# Kalibracija2.net
KiCad netlist of a schematic drawn in Altium Designer
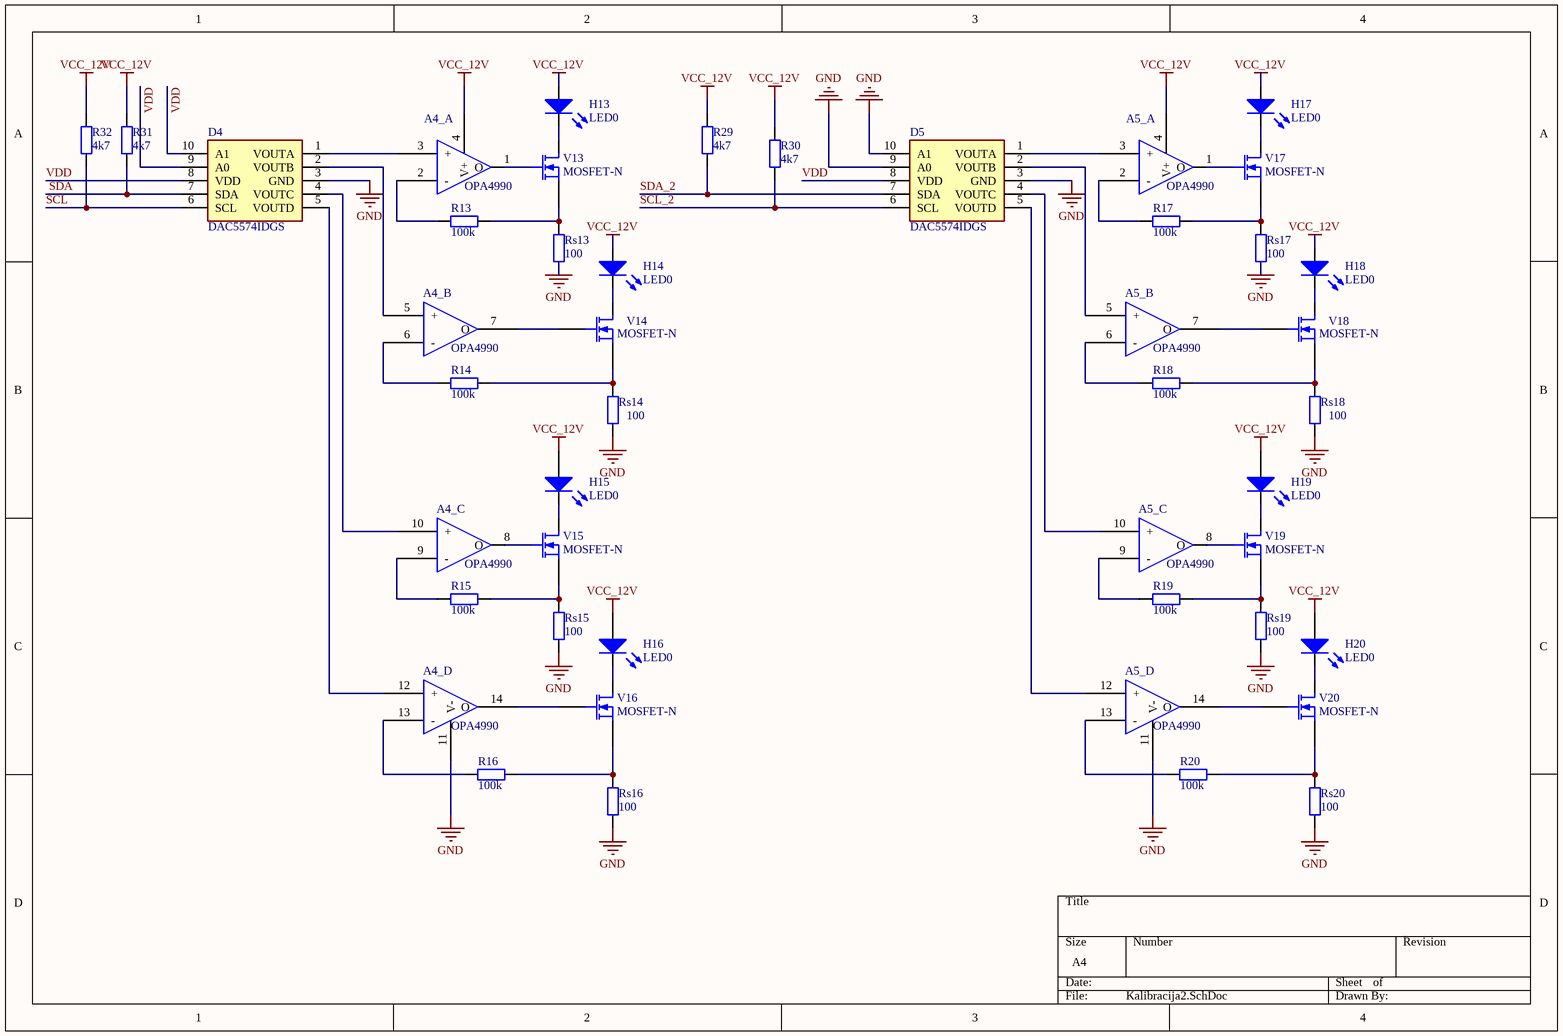
[diagram p0: Kalibracija2.SchDoc]

(export (version "E")
  (design (tool "Eeschema 10.0.6"))
  (components
    (comp (ref "A4_")
      (value "OPA4990")
      (footprint "SOIC127P600X175-14N")
      (libsource (lib "Kalibracija") (part "OPA4990"))
    )
    (comp (ref "A5_")
      (value "OPA4990")
      (footprint "SOIC127P600X175-14N")
      (libsource (lib "Kalibracija") (part "OPA4990"))
    )
    (comp (ref "D4")
      (value "DAC5574IDGS")
      (footprint "SamacSys:SOP50P490X110-10N")
      (description "Integrated Circuit")
      (fields
        (field (name "MOUSER PART NUMBER") "595-DAC5574IDGS")
        (field (name "RS PART NUMBER") "6621533P")
      )
      (libsource (lib "*") (part "DAC5574IDGS"))
    )
    (comp (ref "D5")
      (value "DAC5574IDGS")
      (footprint "SamacSys:SOP50P490X110-10N")
      (description "Integrated Circuit")
      (fields
        (field (name "MOUSER PART NUMBER") "595-DAC5574IDGS")
        (field (name "RS PART NUMBER") "6621533P")
      )
      (libsource (lib "*") (part "DAC5574IDGS"))
    )
    (comp (ref "H13")
      (value "LED0")
      (footprint "HDR1X2")
      (description "Typical INFRARED GaAs LED")
      (fields (field (name "PUBLISHER") "Altium Limited"))
      (libsource (lib "Miscellaneous Devices") (part "LED0"))
    )
    (comp (ref "H14")
      (value "LED0")
      (footprint "HDR1X2")
      (description "Typical INFRARED GaAs LED")
      (fields (field (name "PUBLISHER") "Altium Limited"))
      (libsource (lib "Miscellaneous Devices") (part "LED0"))
    )
    (comp (ref "H15")
      (value "LED0")
      (footprint "HDR1X2")
      (description "Typical INFRARED GaAs LED")
      (fields (field (name "PUBLISHER") "Altium Limited"))
      (libsource (lib "Miscellaneous Devices") (part "LED0"))
    )
    (comp (ref "H16")
      (value "LED0")
      (footprint "HDR1X2")
      (description "Typical INFRARED GaAs LED")
      (fields (field (name "PUBLISHER") "Altium Limited"))
      (libsource (lib "Miscellaneous Devices") (part "LED0"))
    )
    (comp (ref "H17")
      (value "LED0")
      (footprint "HDR1X2")
      (description "Typical INFRARED GaAs LED")
      (fields (field (name "PUBLISHER") "Altium Limited"))
      (libsource (lib "Miscellaneous Devices") (part "LED0"))
    )
    (comp (ref "H18")
      (value "LED0")
      (footprint "HDR1X2")
      (description "Typical INFRARED GaAs LED")
      (fields (field (name "PUBLISHER") "Altium Limited"))
      (libsource (lib "Miscellaneous Devices") (part "LED0"))
    )
    (comp (ref "H19")
      (value "LED0")
      (footprint "HDR1X2")
      (description "Typical INFRARED GaAs LED")
      (fields (field (name "PUBLISHER") "Altium Limited"))
      (libsource (lib "Miscellaneous Devices") (part "LED0"))
    )
    (comp (ref "H20")
      (value "LED0")
      (footprint "HDR1X2")
      (description "Typical INFRARED GaAs LED")
      (fields (field (name "PUBLISHER") "Altium Limited"))
      (libsource (lib "Miscellaneous Devices") (part "LED0"))
    )
    (comp (ref "R13")
      (value "100k")
      (footprint "AXIAL-0.4")
      (description "Resistor")
      (fields (field (name "PUBLISHER") "Altium Limited"))
      (libsource (lib "Miscellaneous Devices") (part "Res2"))
    )
    (comp (ref "R14")
      (value "100k")
      (footprint "AXIAL-0.4")
      (description "Resistor")
      (fields (field (name "PUBLISHER") "Altium Limited"))
      (libsource (lib "Miscellaneous Devices") (part "Res2"))
    )
    (comp (ref "R15")
      (value "100k")
      (footprint "AXIAL-0.4")
      (description "Resistor")
      (fields (field (name "PUBLISHER") "Altium Limited"))
      (libsource (lib "Miscellaneous Devices") (part "Res2"))
    )
    (comp (ref "R16")
      (value "100k")
      (footprint "AXIAL-0.4")
      (description "Resistor")
      (fields (field (name "PUBLISHER") "Altium Limited"))
      (libsource (lib "Miscellaneous Devices") (part "Res2"))
    )
    (comp (ref "R17")
      (value "100k")
      (footprint "AXIAL-0.4")
      (description "Resistor")
      (fields (field (name "PUBLISHER") "Altium Limited"))
      (libsource (lib "Miscellaneous Devices") (part "Res2"))
    )
    (comp (ref "R18")
      (value "100k")
      (footprint "AXIAL-0.4")
      (description "Resistor")
      (fields (field (name "PUBLISHER") "Altium Limited"))
      (libsource (lib "Miscellaneous Devices") (part "Res2"))
    )
    (comp (ref "R19")
      (value "100k")
      (footprint "AXIAL-0.4")
      (description "Resistor")
      (fields (field (name "PUBLISHER") "Altium Limited"))
      (libsource (lib "Miscellaneous Devices") (part "Res2"))
    )
    (comp (ref "R20")
      (value "100k")
      (footprint "AXIAL-0.4")
      (description "Resistor")
      (fields (field (name "PUBLISHER") "Altium Limited"))
      (libsource (lib "Miscellaneous Devices") (part "Res2"))
    )
    (comp (ref "R29")
      (value "4k7")
      (footprint "6-0805_N")
      (description "Resistor")
      (fields (field (name "PUBLISHER") "Altium Limited"))
      (libsource (lib "") (part "Res2_2"))
    )
    (comp (ref "R30")
      (value "4k7")
      (footprint "6-0805_N")
      (description "Resistor")
      (fields (field (name "PUBLISHER") "Altium Limited"))
      (libsource (lib "") (part "Res2_2"))
    )
    (comp (ref "R31")
      (value "4k7")
      (footprint "6-0805_N")
      (description "Resistor")
      (fields (field (name "PUBLISHER") "Altium Limited"))
      (libsource (lib "") (part "Res2_2"))
    )
    (comp (ref "R32")
      (value "4k7")
      (footprint "6-0805_N")
      (description "Resistor")
      (fields (field (name "PUBLISHER") "Altium Limited"))
      (libsource (lib "") (part "Res2_2"))
    )
    (comp (ref "Rs13")
      (value "100")
      (footprint "AXIAL-0.4")
      (description "Resistor")
      (fields (field (name "PUBLISHER") "Altium Limited"))
      (libsource (lib "") (part "Res2_1"))
    )
    (comp (ref "Rs14")
      (value "100")
      (footprint "AXIAL-0.4")
      (description "Resistor")
      (fields (field (name "PUBLISHER") "Altium Limited"))
      (libsource (lib "") (part "Res2_1"))
    )
    (comp (ref "Rs15")
      (value "100")
      (footprint "AXIAL-0.4")
      (description "Resistor")
      (fields (field (name "PUBLISHER") "Altium Limited"))
      (libsource (lib "") (part "Res2_1"))
    )
    (comp (ref "Rs16")
      (value "100")
      (footprint "AXIAL-0.4")
      (description "Resistor")
      (fields (field (name "PUBLISHER") "Altium Limited"))
      (libsource (lib "") (part "Res2_1"))
    )
    (comp (ref "Rs17")
      (value "100")
      (footprint "AXIAL-0.4")
      (description "Resistor")
      (fields (field (name "PUBLISHER") "Altium Limited"))
      (libsource (lib "") (part "Res2_1"))
    )
    (comp (ref "Rs18")
      (value "100")
      (footprint "AXIAL-0.4")
      (description "Resistor")
      (fields (field (name "PUBLISHER") "Altium Limited"))
      (libsource (lib "") (part "Res2_1"))
    )
    (comp (ref "Rs19")
      (value "100")
      (footprint "AXIAL-0.4")
      (description "Resistor")
      (fields (field (name "PUBLISHER") "Altium Limited"))
      (libsource (lib "") (part "Res2_1"))
    )
    (comp (ref "Rs20")
      (value "100")
      (footprint "AXIAL-0.4")
      (description "Resistor")
      (fields (field (name "PUBLISHER") "Altium Limited"))
      (libsource (lib "") (part "Res2_1"))
    )
    (comp (ref "V13")
      (value "MOSFET-N")
      (footprint "TO-92")
      (description "N-Channel MOSFET")
      (fields (field (name "PUBLISHER") "Altium Limited"))
      (libsource (lib "Miscellaneous Devices") (part "MOSFET-N"))
    )
    (comp (ref "V14")
      (value "MOSFET-N")
      (footprint "TO-92")
      (description "N-Channel MOSFET")
      (fields (field (name "PUBLISHER") "Altium Limited"))
      (libsource (lib "Miscellaneous Devices") (part "MOSFET-N"))
    )
    (comp (ref "V15")
      (value "MOSFET-N")
      (footprint "TO-92")
      (description "N-Channel MOSFET")
      (fields (field (name "PUBLISHER") "Altium Limited"))
      (libsource (lib "Miscellaneous Devices") (part "MOSFET-N"))
    )
    (comp (ref "V16")
      (value "MOSFET-N")
      (footprint "TO-92")
      (description "N-Channel MOSFET")
      (fields (field (name "PUBLISHER") "Altium Limited"))
      (libsource (lib "Miscellaneous Devices") (part "MOSFET-N"))
    )
    (comp (ref "V17")
      (value "MOSFET-N")
      (footprint "TO-92")
      (description "N-Channel MOSFET")
      (fields (field (name "PUBLISHER") "Altium Limited"))
      (libsource (lib "Miscellaneous Devices") (part "MOSFET-N"))
    )
    (comp (ref "V18")
      (value "MOSFET-N")
      (footprint "TO-92")
      (description "N-Channel MOSFET")
      (fields (field (name "PUBLISHER") "Altium Limited"))
      (libsource (lib "Miscellaneous Devices") (part "MOSFET-N"))
    )
    (comp (ref "V19")
      (value "MOSFET-N")
      (footprint "TO-92")
      (description "N-Channel MOSFET")
      (fields (field (name "PUBLISHER") "Altium Limited"))
      (libsource (lib "Miscellaneous Devices") (part "MOSFET-N"))
    )
    (comp (ref "V20")
      (value "MOSFET-N")
      (footprint "TO-92")
      (description "N-Channel MOSFET")
      (fields (field (name "PUBLISHER") "Altium Limited"))
      (libsource (lib "Miscellaneous Devices") (part "MOSFET-N"))
    )
  )
  (nets
    (net (code "1") (name "/SCL") (class "Default")
      (node (ref "D4") (pin "6") (pinfunction "SCL_6") (pintype "passive"))
      (node (ref "R32") (pin "2") (pinfunction "2_2") (pintype "passive"))
    )
    (net (code "2") (name "/SCL_2") (class "Default")
      (node (ref "D5") (pin "6") (pinfunction "SCL_6") (pintype "passive"))
      (node (ref "R30") (pin "2") (pinfunction "2_2") (pintype "passive"))
    )
    (net (code "3") (name "/SDA") (class "Default")
      (node (ref "D4") (pin "7") (pinfunction "SDA_7") (pintype "passive"))
      (node (ref "R31") (pin "2") (pinfunction "2_2") (pintype "passive"))
    )
    (net (code "4") (name "/SDA_2") (class "Default")
      (node (ref "D5") (pin "7") (pinfunction "SDA_7") (pintype "passive"))
      (node (ref "R29") (pin "2") (pinfunction "2_2") (pintype "passive"))
    )
    (net (code "5") (name "/VDD") (class "Default")
      (node (ref "D4") (pin "10") (pinfunction "A1_10") (pintype "passive"))
      (node (ref "D4") (pin "8") (pinfunction "VDD_8") (pintype "passive"))
      (node (ref "D4") (pin "9") (pinfunction "A0_9") (pintype "passive"))
      (node (ref "D5") (pin "8") (pinfunction "VDD_8") (pintype "passive"))
    )
    (net (code "6") (name "GND") (class "Default")
      (node (ref "A4_") (pin "11") (pinfunction "V-_11") (pintype "power_in"))
      (node (ref "A5_") (pin "11") (pinfunction "V-_11") (pintype "power_in"))
      (node (ref "D4") (pin "3") (pinfunction "GND_3") (pintype "passive"))
      (node (ref "D5") (pin "10") (pinfunction "A1_10") (pintype "passive"))
      (node (ref "D5") (pin "3") (pinfunction "GND_3") (pintype "passive"))
      (node (ref "D5") (pin "9") (pinfunction "A0_9") (pintype "passive"))
      (node (ref "Rs13") (pin "1") (pinfunction "1_1") (pintype "passive"))
      (node (ref "Rs14") (pin "1") (pinfunction "1_1") (pintype "passive"))
      (node (ref "Rs15") (pin "1") (pinfunction "1_1") (pintype "passive"))
      (node (ref "Rs16") (pin "1") (pinfunction "1_1") (pintype "passive"))
      (node (ref "Rs17") (pin "1") (pinfunction "1_1") (pintype "passive"))
      (node (ref "Rs18") (pin "1") (pinfunction "1_1") (pintype "passive"))
      (node (ref "Rs19") (pin "1") (pinfunction "1_1") (pintype "passive"))
      (node (ref "Rs20") (pin "1") (pinfunction "1_1") (pintype "passive"))
    )
    (net (code "7") (name "Net-(A4_A-+)") (class "Default")
      (node (ref "A4_") (pin "3") (pinfunction "+_3") (pintype "passive"))
      (node (ref "D4") (pin "1") (pinfunction "VOUTA_1") (pintype "passive"))
    )
    (net (code "8") (name "Net-(A4_A--)") (class "Default")
      (node (ref "A4_") (pin "2") (pinfunction "-_2") (pintype "passive"))
      (node (ref "R13") (pin "1") (pinfunction "1_1") (pintype "passive"))
    )
    (net (code "9") (name "Net-(A4_A-O)") (class "Default")
      (node (ref "A4_") (pin "1") (pinfunction "O_1") (pintype "passive"))
      (node (ref "V13") (pin "2") (pinfunction "G_2") (pintype "passive"))
    )
    (net (code "10") (name "Net-(A4_B-+)") (class "Default")
      (node (ref "A4_") (pin "5") (pinfunction "+_5") (pintype "passive"))
      (node (ref "D4") (pin "2") (pinfunction "VOUTB_2") (pintype "passive"))
    )
    (net (code "11") (name "Net-(A4_B--)") (class "Default")
      (node (ref "A4_") (pin "6") (pinfunction "-_6") (pintype "passive"))
      (node (ref "R14") (pin "1") (pinfunction "1_1") (pintype "passive"))
    )
    (net (code "12") (name "Net-(A4_B-O)") (class "Default")
      (node (ref "A4_") (pin "7") (pinfunction "O_7") (pintype "passive"))
      (node (ref "V14") (pin "2") (pinfunction "G_2") (pintype "passive"))
    )
    (net (code "13") (name "Net-(A4_C-+)") (class "Default")
      (node (ref "A4_") (pin "10") (pinfunction "+_10") (pintype "passive"))
      (node (ref "D4") (pin "4") (pinfunction "VOUTC_4") (pintype "passive"))
    )
    (net (code "14") (name "Net-(A4_C--)") (class "Default")
      (node (ref "A4_") (pin "9") (pinfunction "-_9") (pintype "passive"))
      (node (ref "R15") (pin "1") (pinfunction "1_1") (pintype "passive"))
    )
    (net (code "15") (name "Net-(A4_C-O)") (class "Default")
      (node (ref "A4_") (pin "8") (pinfunction "O_8") (pintype "passive"))
      (node (ref "V15") (pin "2") (pinfunction "G_2") (pintype "passive"))
    )
    (net (code "16") (name "Net-(A4_D-+)") (class "Default")
      (node (ref "A4_") (pin "12") (pinfunction "+_12") (pintype "passive"))
      (node (ref "D4") (pin "5") (pinfunction "VOUTD_5") (pintype "passive"))
    )
    (net (code "17") (name "Net-(A4_D--)") (class "Default")
      (node (ref "A4_") (pin "13") (pinfunction "-_13") (pintype "passive"))
      (node (ref "R16") (pin "1") (pinfunction "1_1") (pintype "passive"))
    )
    (net (code "18") (name "Net-(A4_D-O)") (class "Default")
      (node (ref "A4_") (pin "14") (pinfunction "O_14") (pintype "passive"))
      (node (ref "V16") (pin "2") (pinfunction "G_2") (pintype "passive"))
    )
    (net (code "19") (name "Net-(A5_A-+)") (class "Default")
      (node (ref "A5_") (pin "3") (pinfunction "+_3") (pintype "passive"))
      (node (ref "D5") (pin "1") (pinfunction "VOUTA_1") (pintype "passive"))
    )
    (net (code "20") (name "Net-(A5_A--)") (class "Default")
      (node (ref "A5_") (pin "2") (pinfunction "-_2") (pintype "passive"))
      (node (ref "R17") (pin "1") (pinfunction "1_1") (pintype "passive"))
    )
    (net (code "21") (name "Net-(A5_A-O)") (class "Default")
      (node (ref "A5_") (pin "1") (pinfunction "O_1") (pintype "passive"))
      (node (ref "V17") (pin "2") (pinfunction "G_2") (pintype "passive"))
    )
    (net (code "22") (name "Net-(A5_B-+)") (class "Default")
      (node (ref "A5_") (pin "5") (pinfunction "+_5") (pintype "passive"))
      (node (ref "D5") (pin "2") (pinfunction "VOUTB_2") (pintype "passive"))
    )
    (net (code "23") (name "Net-(A5_B--)") (class "Default")
      (node (ref "A5_") (pin "6") (pinfunction "-_6") (pintype "passive"))
      (node (ref "R18") (pin "1") (pinfunction "1_1") (pintype "passive"))
    )
    (net (code "24") (name "Net-(A5_B-O)") (class "Default")
      (node (ref "A5_") (pin "7") (pinfunction "O_7") (pintype "passive"))
      (node (ref "V18") (pin "2") (pinfunction "G_2") (pintype "passive"))
    )
    (net (code "25") (name "Net-(A5_C-+)") (class "Default")
      (node (ref "A5_") (pin "10") (pinfunction "+_10") (pintype "passive"))
      (node (ref "D5") (pin "4") (pinfunction "VOUTC_4") (pintype "passive"))
    )
    (net (code "26") (name "Net-(A5_C--)") (class "Default")
      (node (ref "A5_") (pin "9") (pinfunction "-_9") (pintype "passive"))
      (node (ref "R19") (pin "1") (pinfunction "1_1") (pintype "passive"))
    )
    (net (code "27") (name "Net-(A5_C-O)") (class "Default")
      (node (ref "A5_") (pin "8") (pinfunction "O_8") (pintype "passive"))
      (node (ref "V19") (pin "2") (pinfunction "G_2") (pintype "passive"))
    )
    (net (code "28") (name "Net-(A5_D-+)") (class "Default")
      (node (ref "A5_") (pin "12") (pinfunction "+_12") (pintype "passive"))
      (node (ref "D5") (pin "5") (pinfunction "VOUTD_5") (pintype "passive"))
    )
    (net (code "29") (name "Net-(A5_D--)") (class "Default")
      (node (ref "A5_") (pin "13") (pinfunction "-_13") (pintype "passive"))
      (node (ref "R20") (pin "1") (pinfunction "1_1") (pintype "passive"))
    )
    (net (code "30") (name "Net-(A5_D-O)") (class "Default")
      (node (ref "A5_") (pin "14") (pinfunction "O_14") (pintype "passive"))
      (node (ref "V20") (pin "2") (pinfunction "G_2") (pintype "passive"))
    )
    (net (code "31") (name "Net-(H13-K)") (class "Default")
      (node (ref "H13") (pin "2") (pinfunction "K_2") (pintype "passive"))
      (node (ref "V13") (pin "1") (pinfunction "D_1") (pintype "passive"))
    )
    (net (code "32") (name "Net-(H14-K)") (class "Default")
      (node (ref "H14") (pin "2") (pinfunction "K_2") (pintype "passive"))
      (node (ref "V14") (pin "1") (pinfunction "D_1") (pintype "passive"))
    )
    (net (code "33") (name "Net-(H15-K)") (class "Default")
      (node (ref "H15") (pin "2") (pinfunction "K_2") (pintype "passive"))
      (node (ref "V15") (pin "1") (pinfunction "D_1") (pintype "passive"))
    )
    (net (code "34") (name "Net-(H16-K)") (class "Default")
      (node (ref "H16") (pin "2") (pinfunction "K_2") (pintype "passive"))
      (node (ref "V16") (pin "1") (pinfunction "D_1") (pintype "passive"))
    )
    (net (code "35") (name "Net-(H17-K)") (class "Default")
      (node (ref "H17") (pin "2") (pinfunction "K_2") (pintype "passive"))
      (node (ref "V17") (pin "1") (pinfunction "D_1") (pintype "passive"))
    )
    (net (code "36") (name "Net-(H18-K)") (class "Default")
      (node (ref "H18") (pin "2") (pinfunction "K_2") (pintype "passive"))
      (node (ref "V18") (pin "1") (pinfunction "D_1") (pintype "passive"))
    )
    (net (code "37") (name "Net-(H19-K)") (class "Default")
      (node (ref "H19") (pin "2") (pinfunction "K_2") (pintype "passive"))
      (node (ref "V19") (pin "1") (pinfunction "D_1") (pintype "passive"))
    )
    (net (code "38") (name "Net-(H20-K)") (class "Default")
      (node (ref "H20") (pin "2") (pinfunction "K_2") (pintype "passive"))
      (node (ref "V20") (pin "1") (pinfunction "D_1") (pintype "passive"))
    )
    (net (code "39") (name "Net-(V13-S)") (class "Default")
      (node (ref "R13") (pin "2") (pinfunction "2_2") (pintype "passive"))
      (node (ref "Rs13") (pin "2") (pinfunction "2_2") (pintype "passive"))
      (node (ref "V13") (pin "3") (pinfunction "S_3") (pintype "passive"))
    )
    (net (code "40") (name "Net-(V14-S)") (class "Default")
      (node (ref "R14") (pin "2") (pinfunction "2_2") (pintype "passive"))
      (node (ref "Rs14") (pin "2") (pinfunction "2_2") (pintype "passive"))
      (node (ref "V14") (pin "3") (pinfunction "S_3") (pintype "passive"))
    )
    (net (code "41") (name "Net-(V15-S)") (class "Default")
      (node (ref "R15") (pin "2") (pinfunction "2_2") (pintype "passive"))
      (node (ref "Rs15") (pin "2") (pinfunction "2_2") (pintype "passive"))
      (node (ref "V15") (pin "3") (pinfunction "S_3") (pintype "passive"))
    )
    (net (code "42") (name "Net-(V16-S)") (class "Default")
      (node (ref "R16") (pin "2") (pinfunction "2_2") (pintype "passive"))
      (node (ref "Rs16") (pin "2") (pinfunction "2_2") (pintype "passive"))
      (node (ref "V16") (pin "3") (pinfunction "S_3") (pintype "passive"))
    )
    (net (code "43") (name "Net-(V17-S)") (class "Default")
      (node (ref "R17") (pin "2") (pinfunction "2_2") (pintype "passive"))
      (node (ref "Rs17") (pin "2") (pinfunction "2_2") (pintype "passive"))
      (node (ref "V17") (pin "3") (pinfunction "S_3") (pintype "passive"))
    )
    (net (code "44") (name "Net-(V18-S)") (class "Default")
      (node (ref "R18") (pin "2") (pinfunction "2_2") (pintype "passive"))
      (node (ref "Rs18") (pin "2") (pinfunction "2_2") (pintype "passive"))
      (node (ref "V18") (pin "3") (pinfunction "S_3") (pintype "passive"))
    )
    (net (code "45") (name "Net-(V19-S)") (class "Default")
      (node (ref "R19") (pin "2") (pinfunction "2_2") (pintype "passive"))
      (node (ref "Rs19") (pin "2") (pinfunction "2_2") (pintype "passive"))
      (node (ref "V19") (pin "3") (pinfunction "S_3") (pintype "passive"))
    )
    (net (code "46") (name "Net-(V20-S)") (class "Default")
      (node (ref "R20") (pin "2") (pinfunction "2_2") (pintype "passive"))
      (node (ref "Rs20") (pin "2") (pinfunction "2_2") (pintype "passive"))
      (node (ref "V20") (pin "3") (pinfunction "S_3") (pintype "passive"))
    )
    (net (code "47") (name "VCC_12V") (class "Default")
      (node (ref "A4_") (pin "4") (pinfunction "V+_4") (pintype "power_in"))
      (node (ref "A5_") (pin "4") (pinfunction "V+_4") (pintype "power_in"))
      (node (ref "H13") (pin "1") (pinfunction "A_1") (pintype "passive"))
      (node (ref "H14") (pin "1") (pinfunction "A_1") (pintype "passive"))
      (node (ref "H15") (pin "1") (pinfunction "A_1") (pintype "passive"))
      (node (ref "H16") (pin "1") (pinfunction "A_1") (pintype "passive"))
      (node (ref "H17") (pin "1") (pinfunction "A_1") (pintype "passive"))
      (node (ref "H18") (pin "1") (pinfunction "A_1") (pintype "passive"))
      (node (ref "H19") (pin "1") (pinfunction "A_1") (pintype "passive"))
      (node (ref "H20") (pin "1") (pinfunction "A_1") (pintype "passive"))
      (node (ref "R29") (pin "1") (pinfunction "1_1") (pintype "passive"))
      (node (ref "R30") (pin "1") (pinfunction "1_1") (pintype "passive"))
      (node (ref "R31") (pin "1") (pinfunction "1_1") (pintype "passive"))
      (node (ref "R32") (pin "1") (pinfunction "1_1") (pintype "passive"))
    )
  )
)
